# footswitch.net
KiCad netlist of a schematic drawn in EAGLE
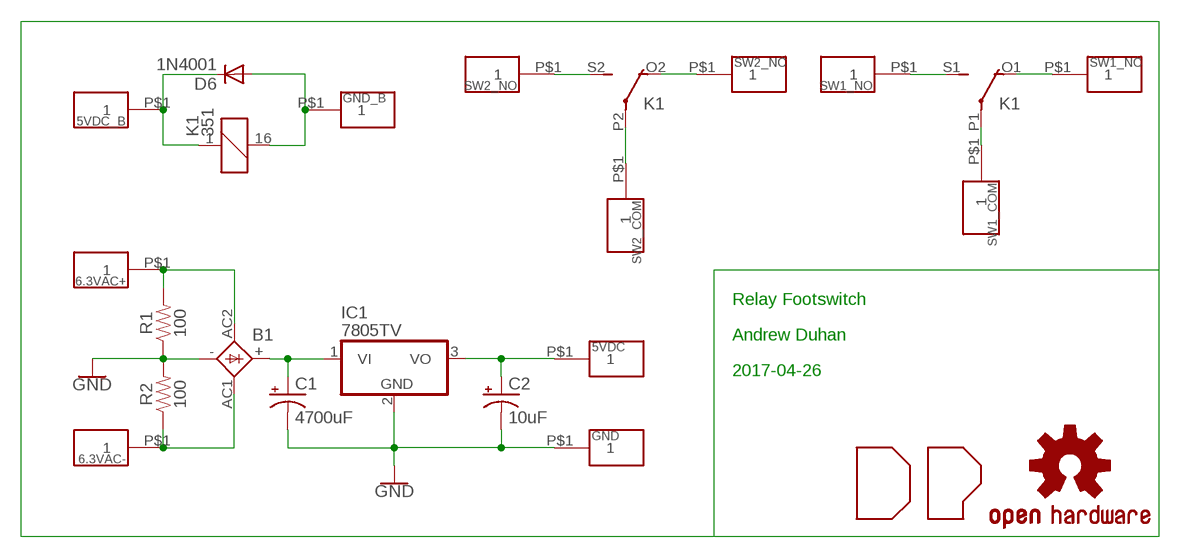
[diagram p0: schematic, sheet 1]

(export (version "E")
  (design (tool "Eeschema 10.0.6"))
  (components
    (comp (ref "5VDC")
      (value "TURRET_LUG_1540")
      (footprint "eagle-import:TURRET_LUG_1540")
      (libsource (lib "eagle-import") (part "TURRET_LUG_1540"))
    )
    (comp (ref "5VDC_B")
      (value "TURRET_LUG_1540")
      (footprint "eagle-import:TURRET_LUG_1540")
      (libsource (lib "eagle-import") (part "TURRET_LUG_1540"))
    )
    (comp (ref "6.3VAC+")
      (value "TURRET_LUG_1540")
      (footprint "eagle-import:TURRET_LUG_1540")
      (libsource (lib "eagle-import") (part "TURRET_LUG_1540"))
    )
    (comp (ref "6.3VAC-")
      (value "TURRET_LUG_1540")
      (footprint "eagle-import:TURRET_LUG_1540")
      (libsource (lib "eagle-import") (part "TURRET_LUG_1540"))
    )
    (comp (ref "B1")
      (value "GBU4")
      (footprint "eagle-import:GBU4S")
      (libsource (lib "eagle-import") (part "GBU4"))
    )
    (comp (ref "C1")
      (value "4700uF")
      (footprint "eagle-import:E7,5-18")
      (libsource (lib "eagle-import") (part "CPOL-USE7.5-18"))
    )
    (comp (ref "C2")
      (value "10uF")
      (footprint "eagle-import:CPOL-RADIAL-2.5MM-5MM")
      (libsource (lib "eagle-import") (part "10UF-POLAR-RADIAL-2.5MM-25V-20%"))
    )
    (comp (ref "D6")
      (value "1N4001")
      (footprint "eagle-import:DO41-10")
      (libsource (lib "eagle-import") (part "1N4004"))
    )
    (comp (ref "GND")
      (value "TURRET_LUG_1540")
      (footprint "eagle-import:TURRET_LUG_1540")
      (libsource (lib "eagle-import") (part "TURRET_LUG_1540"))
    )
    (comp (ref "GND_B")
      (value "TURRET_LUG_1540")
      (footprint "eagle-import:TURRET_LUG_1540")
      (libsource (lib "eagle-import") (part "TURRET_LUG_1540"))
    )
    (comp (ref "IC1")
      (value "7805TV")
      (footprint "eagle-import:TO220V")
      (libsource (lib "eagle-import") (part "78TV05"))
    )
    (comp (ref "K1")
      (value "351")
      (footprint "eagle-import:351")
      (libsource (lib "eagle-import") (part "351"))
    )
    (comp (ref "LOGO1")
      (value "OSHW-LOGOMINI")
      (footprint "eagle-import:OSHW-LOGO-MINI")
      (libsource (lib "eagle-import") (part "OSHW-LOGOMINI"))
    )
    (comp (ref "LOGO2")
      (value "OSHW-LOGOMINI")
      (footprint "eagle-import:OSHW-LOGO-MINI")
      (libsource (lib "eagle-import") (part "OSHW-LOGOMINI"))
    )
    (comp (ref "R1")
      (value "100")
      (footprint "eagle-import:AXIAL-0.3")
      (libsource (lib "eagle-import") (part "RESISTORAXIAL-0.3"))
    )
    (comp (ref "R2")
      (value "100")
      (footprint "eagle-import:AXIAL-0.3")
      (libsource (lib "eagle-import") (part "RESISTORAXIAL-0.3"))
    )
    (comp (ref "SW1_COM")
      (value "TURRET_LUG_1540")
      (footprint "eagle-import:TURRET_LUG_1540")
      (libsource (lib "eagle-import") (part "TURRET_LUG_1540"))
    )
    (comp (ref "SW1_NC")
      (value "TURRET_LUG_1540")
      (footprint "eagle-import:TURRET_LUG_1540")
      (libsource (lib "eagle-import") (part "TURRET_LUG_1540"))
    )
    (comp (ref "SW1_NO")
      (value "TURRET_LUG_1540")
      (footprint "eagle-import:TURRET_LUG_1540")
      (libsource (lib "eagle-import") (part "TURRET_LUG_1540"))
    )
    (comp (ref "SW2_COM")
      (value "TURRET_LUG_1540")
      (footprint "eagle-import:TURRET_LUG_1540")
      (libsource (lib "eagle-import") (part "TURRET_LUG_1540"))
    )
    (comp (ref "SW2_NC")
      (value "TURRET_LUG_1540")
      (footprint "eagle-import:TURRET_LUG_1540")
      (libsource (lib "eagle-import") (part "TURRET_LUG_1540"))
    )
    (comp (ref "SW2_NO")
      (value "TURRET_LUG_1540")
      (footprint "eagle-import:TURRET_LUG_1540")
      (libsource (lib "eagle-import") (part "TURRET_LUG_1540"))
    )
    (comp (ref "U$1")
      (value "DP_LOGO")
      (footprint "eagle-import:DP_LOGO")
      (libsource (lib "eagle-import") (part "DP_LOGO"))
    )
    (comp (ref "U$2")
      (value "DP_LOGO")
      (footprint "eagle-import:DP_LOGO")
      (libsource (lib "eagle-import") (part "DP_LOGO"))
    )
  )
  (nets
    (net (code "1") (name "GND") (class "Default")
      (node (ref "B1") (pin "-") (pinfunction "-_-") (pintype "passive"))
      (node (ref "C1") (pin "-") (pinfunction "-_-") (pintype "passive"))
      (node (ref "C2") (pin "2") (pinfunction "-_2") (pintype "passive"))
      (node (ref "GND") (pin "P$1") (pinfunction "1_P$1") (pintype "bidirectional"))
      (node (ref "IC1") (pin "2") (pinfunction "GND_2") (pintype "passive"))
      (node (ref "R1") (pin "P$1") (pinfunction "1_P$1") (pintype "passive"))
      (node (ref "R2") (pin "P$2") (pinfunction "2_P$2") (pintype "passive"))
    )
    (net (code "2") (name "Net-(5VDC-1)") (class "Default")
      (node (ref "5VDC") (pin "P$1") (pinfunction "1_P$1") (pintype "bidirectional"))
      (node (ref "C2") (pin "1") (pinfunction "+_1") (pintype "passive"))
      (node (ref "IC1") (pin "3") (pinfunction "VO_3") (pintype "passive"))
    )
    (net (code "3") (name "Net-(5VDC_B-1)") (class "Default")
      (node (ref "5VDC_B") (pin "P$1") (pinfunction "1_P$1") (pintype "bidirectional"))
      (node (ref "D6") (pin "C") (pinfunction "C_C") (pintype "passive"))
      (node (ref "K1") (pin "1") (pinfunction "1_1") (pintype "passive"))
    )
    (net (code "4") (name "Net-(6.3VAC+-1)") (class "Default")
      (node (ref "6.3VAC+") (pin "P$1") (pinfunction "1_P$1") (pintype "bidirectional"))
      (node (ref "B1") (pin "AC2") (pinfunction "AC1_AC2") (pintype "passive"))
      (node (ref "R1") (pin "P$2") (pinfunction "2_P$2") (pintype "passive"))
    )
    (net (code "5") (name "Net-(6.3VAC--1)") (class "Default")
      (node (ref "6.3VAC-") (pin "P$1") (pinfunction "1_P$1") (pintype "bidirectional"))
      (node (ref "B1") (pin "AC1") (pinfunction "AC2_AC1") (pintype "passive"))
      (node (ref "R2") (pin "P$1") (pinfunction "1_P$1") (pintype "passive"))
    )
    (net (code "6") (name "Net-(GND_B-1)") (class "Default")
      (node (ref "D6") (pin "A") (pinfunction "A_A") (pintype "passive"))
      (node (ref "GND_B") (pin "P$1") (pinfunction "1_P$1") (pintype "bidirectional"))
      (node (ref "K1") (pin "16") (pinfunction "2_16") (pintype "passive"))
    )
    (net (code "7") (name "Net-(IC1-VI)") (class "Default")
      (node (ref "B1") (pin "+") (pinfunction "+_+") (pintype "passive"))
      (node (ref "C1") (pin "+") (pinfunction "+_+") (pintype "passive"))
      (node (ref "IC1") (pin "1") (pinfunction "VI_1") (pintype "input"))
    )
    (net (code "8") (name "Net-(K1B-O)") (class "Default")
      (node (ref "K1") (pin "O1") (pinfunction "O_O1") (pintype "passive"))
      (node (ref "SW1_NC") (pin "P$1") (pinfunction "1_P$1") (pintype "bidirectional"))
    )
    (net (code "9") (name "Net-(K1B-P)") (class "Default")
      (node (ref "K1") (pin "P1") (pinfunction "P_P1") (pintype "passive"))
      (node (ref "SW1_COM") (pin "P$1") (pinfunction "1_P$1") (pintype "bidirectional"))
    )
    (net (code "10") (name "Net-(K1B-S)") (class "Default")
      (node (ref "K1") (pin "S1") (pinfunction "S_S1") (pintype "passive"))
      (node (ref "SW1_NO") (pin "P$1") (pinfunction "1_P$1") (pintype "bidirectional"))
    )
    (net (code "11") (name "Net-(K1C-O)") (class "Default")
      (node (ref "K1") (pin "O2") (pinfunction "O_O2") (pintype "passive"))
      (node (ref "SW2_NC") (pin "P$1") (pinfunction "1_P$1") (pintype "bidirectional"))
    )
    (net (code "12") (name "Net-(K1C-P)") (class "Default")
      (node (ref "K1") (pin "P2") (pinfunction "P_P2") (pintype "passive"))
      (node (ref "SW2_COM") (pin "P$1") (pinfunction "1_P$1") (pintype "bidirectional"))
    )
    (net (code "13") (name "Net-(K1C-S)") (class "Default")
      (node (ref "K1") (pin "S2") (pinfunction "S_S2") (pintype "passive"))
      (node (ref "SW2_NO") (pin "P$1") (pinfunction "1_P$1") (pintype "bidirectional"))
    )
  )
)
